# top.net
KiCad netlist of a schematic drawn in EAGLE
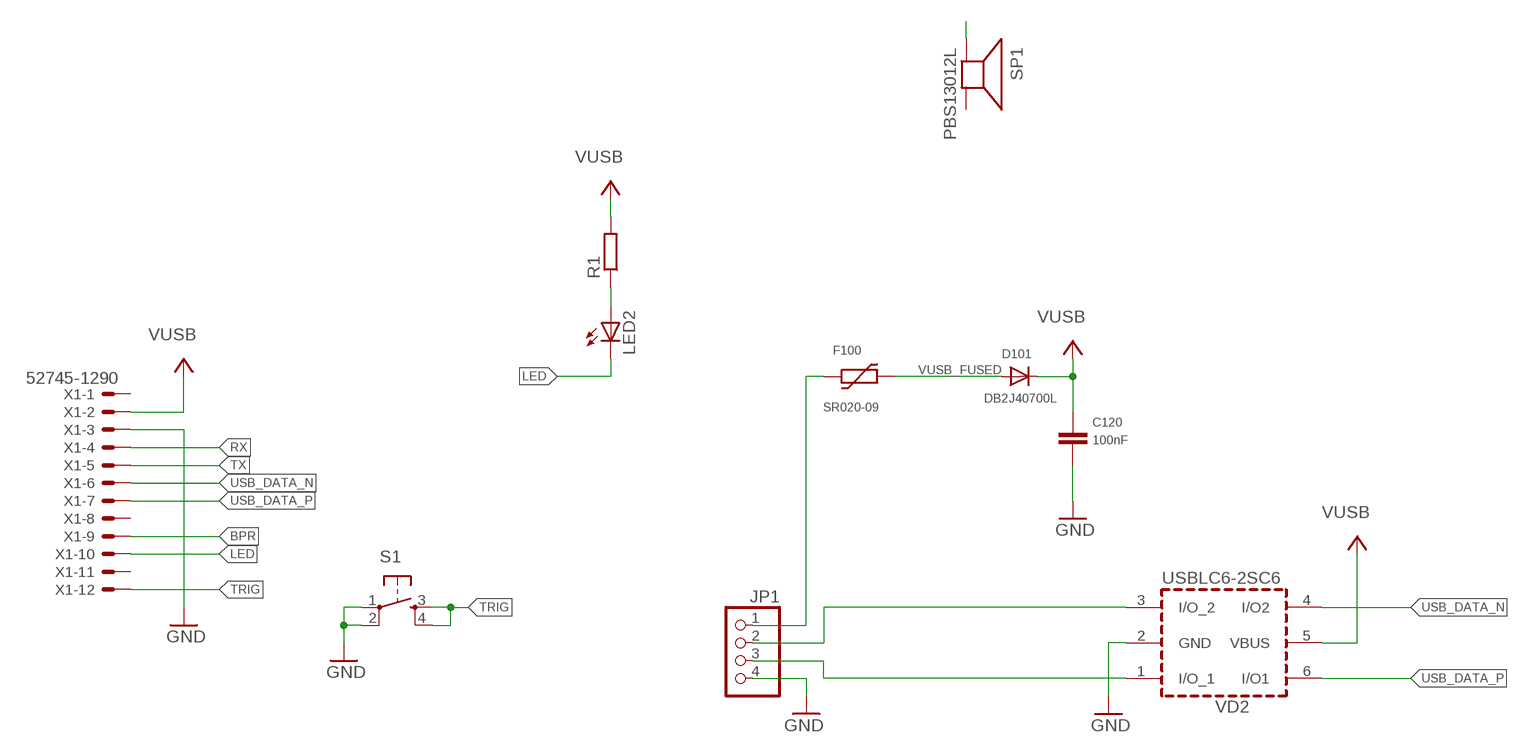
[diagram p0: schematic, sheet 1]

(export (version "E")
  (design (tool "Eeschema 10.0.6"))
  (components
    (comp (ref "C120")
      (value "100nF")
      (footprint "eagle-import:C0603K")
      (libsource (lib "eagle-import") (part "C-EUC0603K"))
    )
    (comp (ref "D101")
      (value "DB2J40700L")
      (footprint "eagle-import:SOD-323F")
      (libsource (lib "eagle-import") (part "DIODESOD-323F"))
    )
    (comp (ref "F100")
      (value "SR020-09")
      (footprint "eagle-import:PTC0805")
      (libsource (lib "eagle-import") (part "FUSE_PTC-0805"))
    )
    (comp (ref "JP1")
      (value "PINHD-1X4")
      (footprint "eagle-import:1X04")
      (libsource (lib "eagle-import") (part "PINHD-1X4"))
    )
    (comp (ref "LED2")
      (value "LEDCHIP-LED0805")
      (footprint "eagle-import:CHIP-LED0805")
      (libsource (lib "eagle-import") (part "LEDCHIP-LED0805"))
    )
    (comp (ref "R1")
      (value "R-EU_R0603")
      (footprint "eagle-import:R0603")
      (libsource (lib "eagle-import") (part "R-EU_R0603"))
    )
    (comp (ref "S1")
      (value "TAC_SWITCHSMD")
      (footprint "eagle-import:TACTILE_SWITCH_SMD")
      (libsource (lib "eagle-import") (part "TAC_SWITCHSMD"))
    )
    (comp (ref "SP1")
      (value "PBS13012L")
      (footprint "eagle-import:AL60P")
      (libsource (lib "eagle-import") (part "SPEAKER/AL60P"))
    )
    (comp (ref "VD2")
      (value "USBLC6-2SC6")
      (footprint "eagle-import:SOT-23-6L")
      (libsource (lib "eagle-import") (part "USBLC6-2SC6"))
    )
    (comp (ref "X1")
      (value "52745-1290")
      (footprint "eagle-import:52745-1290")
      (libsource (lib "eagle-import") (part "52745-1290"))
    )
  )
  (nets
    (net (code "1") (name "/VUSB_FUSED") (class "Default")
      (node (ref "D101") (pin "A") (pinfunction "A_A") (pintype "passive"))
      (node (ref "F100") (pin "2") (pinfunction "2_2") (pintype "passive"))
    )
    (net (code "2") (name "BPR") (class "Default")
      (node (ref "X1") (pin "9") (pinfunction "S_9") (pintype "passive"))
    )
    (net (code "3") (name "GND") (class "Default")
      (node (ref "C120") (pin "2") (pinfunction "2_2") (pintype "passive"))
      (node (ref "JP1") (pin "4") (pinfunction "4_4") (pintype "passive"))
      (node (ref "S1") (pin "1") (pinfunction "1_1") (pintype "passive"))
      (node (ref "S1") (pin "2") (pinfunction "2_2") (pintype "passive"))
      (node (ref "VD2") (pin "2") (pinfunction "GND_2") (pintype "bidirectional"))
      (node (ref "X1") (pin "3") (pinfunction "S_3") (pintype "passive"))
    )
    (net (code "4") (name "LED") (class "Default")
      (node (ref "LED2") (pin "C") (pinfunction "C_C") (pintype "passive"))
      (node (ref "X1") (pin "10") (pinfunction "S_10") (pintype "passive"))
    )
    (net (code "5") (name "Net-(F100-Pad1)") (class "Default")
      (node (ref "F100") (pin "1") (pinfunction "1_1") (pintype "passive"))
      (node (ref "JP1") (pin "1") (pinfunction "1_1") (pintype "passive"))
    )
    (net (code "6") (name "Net-(LED2-PadA)") (class "Default")
      (node (ref "LED2") (pin "A") (pinfunction "A_A") (pintype "passive"))
      (node (ref "R1") (pin "1") (pinfunction "1_1") (pintype "passive"))
    )
    (net (code "7") (name "Net-(VD2-I{slash}O_1)") (class "Default")
      (node (ref "JP1") (pin "3") (pinfunction "3_3") (pintype "passive"))
      (node (ref "VD2") (pin "1") (pinfunction "I/O_1_1") (pintype "bidirectional"))
    )
    (net (code "8") (name "Net-(VD2-I{slash}O_2)") (class "Default")
      (node (ref "JP1") (pin "2") (pinfunction "2_2") (pintype "passive"))
      (node (ref "VD2") (pin "3") (pinfunction "I/O_2_3") (pintype "bidirectional"))
    )
    (net (code "9") (name "RX") (class "Default")
      (node (ref "X1") (pin "4") (pinfunction "S_4") (pintype "passive"))
    )
    (net (code "10") (name "TRIG") (class "Default")
      (node (ref "S1") (pin "3") (pinfunction "3_3") (pintype "passive"))
      (node (ref "S1") (pin "4") (pinfunction "4_4") (pintype "passive"))
      (node (ref "X1") (pin "12") (pinfunction "S_12") (pintype "passive"))
    )
    (net (code "11") (name "TX") (class "Default")
      (node (ref "X1") (pin "5") (pinfunction "S_5") (pintype "passive"))
    )
    (net (code "12") (name "USB_DATA_N") (class "Default")
      (node (ref "VD2") (pin "4") (pinfunction "I/O2_4") (pintype "bidirectional"))
      (node (ref "X1") (pin "6") (pinfunction "S_6") (pintype "passive"))
    )
    (net (code "13") (name "USB_DATA_P") (class "Default")
      (node (ref "VD2") (pin "6") (pinfunction "I/O1_6") (pintype "bidirectional"))
      (node (ref "X1") (pin "7") (pinfunction "S_7") (pintype "passive"))
    )
    (net (code "14") (name "VUSB") (class "Default")
      (node (ref "C120") (pin "1") (pinfunction "1_1") (pintype "passive"))
      (node (ref "D101") (pin "C") (pinfunction "C_C") (pintype "passive"))
      (node (ref "R1") (pin "2") (pinfunction "2_2") (pintype "passive"))
      (node (ref "VD2") (pin "5") (pinfunction "VBUS_5") (pintype "bidirectional"))
      (node (ref "X1") (pin "2") (pinfunction "S_2") (pintype "passive"))
    )
    (net (code "15") (name "unconnected-(SP1-+-Pad1)") (class "Default")
      (node (ref "SP1") (pin "1") (pinfunction "+_1") (pintype "passive"))
    )
    (net (code "16") (name "unconnected-(SP1---Pad2)") (class "Default")
      (node (ref "SP1") (pin "2") (pinfunction "-_2") (pintype "passive"))
    )
    (net (code "17") (name "unconnected-(X1A-S-Pad1)") (class "Default")
      (node (ref "X1") (pin "1") (pinfunction "S_1") (pintype "passive"))
    )
    (net (code "18") (name "unconnected-(X1C-S-Pad11)") (class "Default")
      (node (ref "X1") (pin "11") (pinfunction "S_11") (pintype "passive"))
    )
    (net (code "19") (name "unconnected-(X1K-S-Pad8)") (class "Default")
      (node (ref "X1") (pin "8") (pinfunction "S_8") (pintype "passive"))
    )
  )
)
